# TIMER.net
KiCad netlist of a schematic drawn in Altium Designer
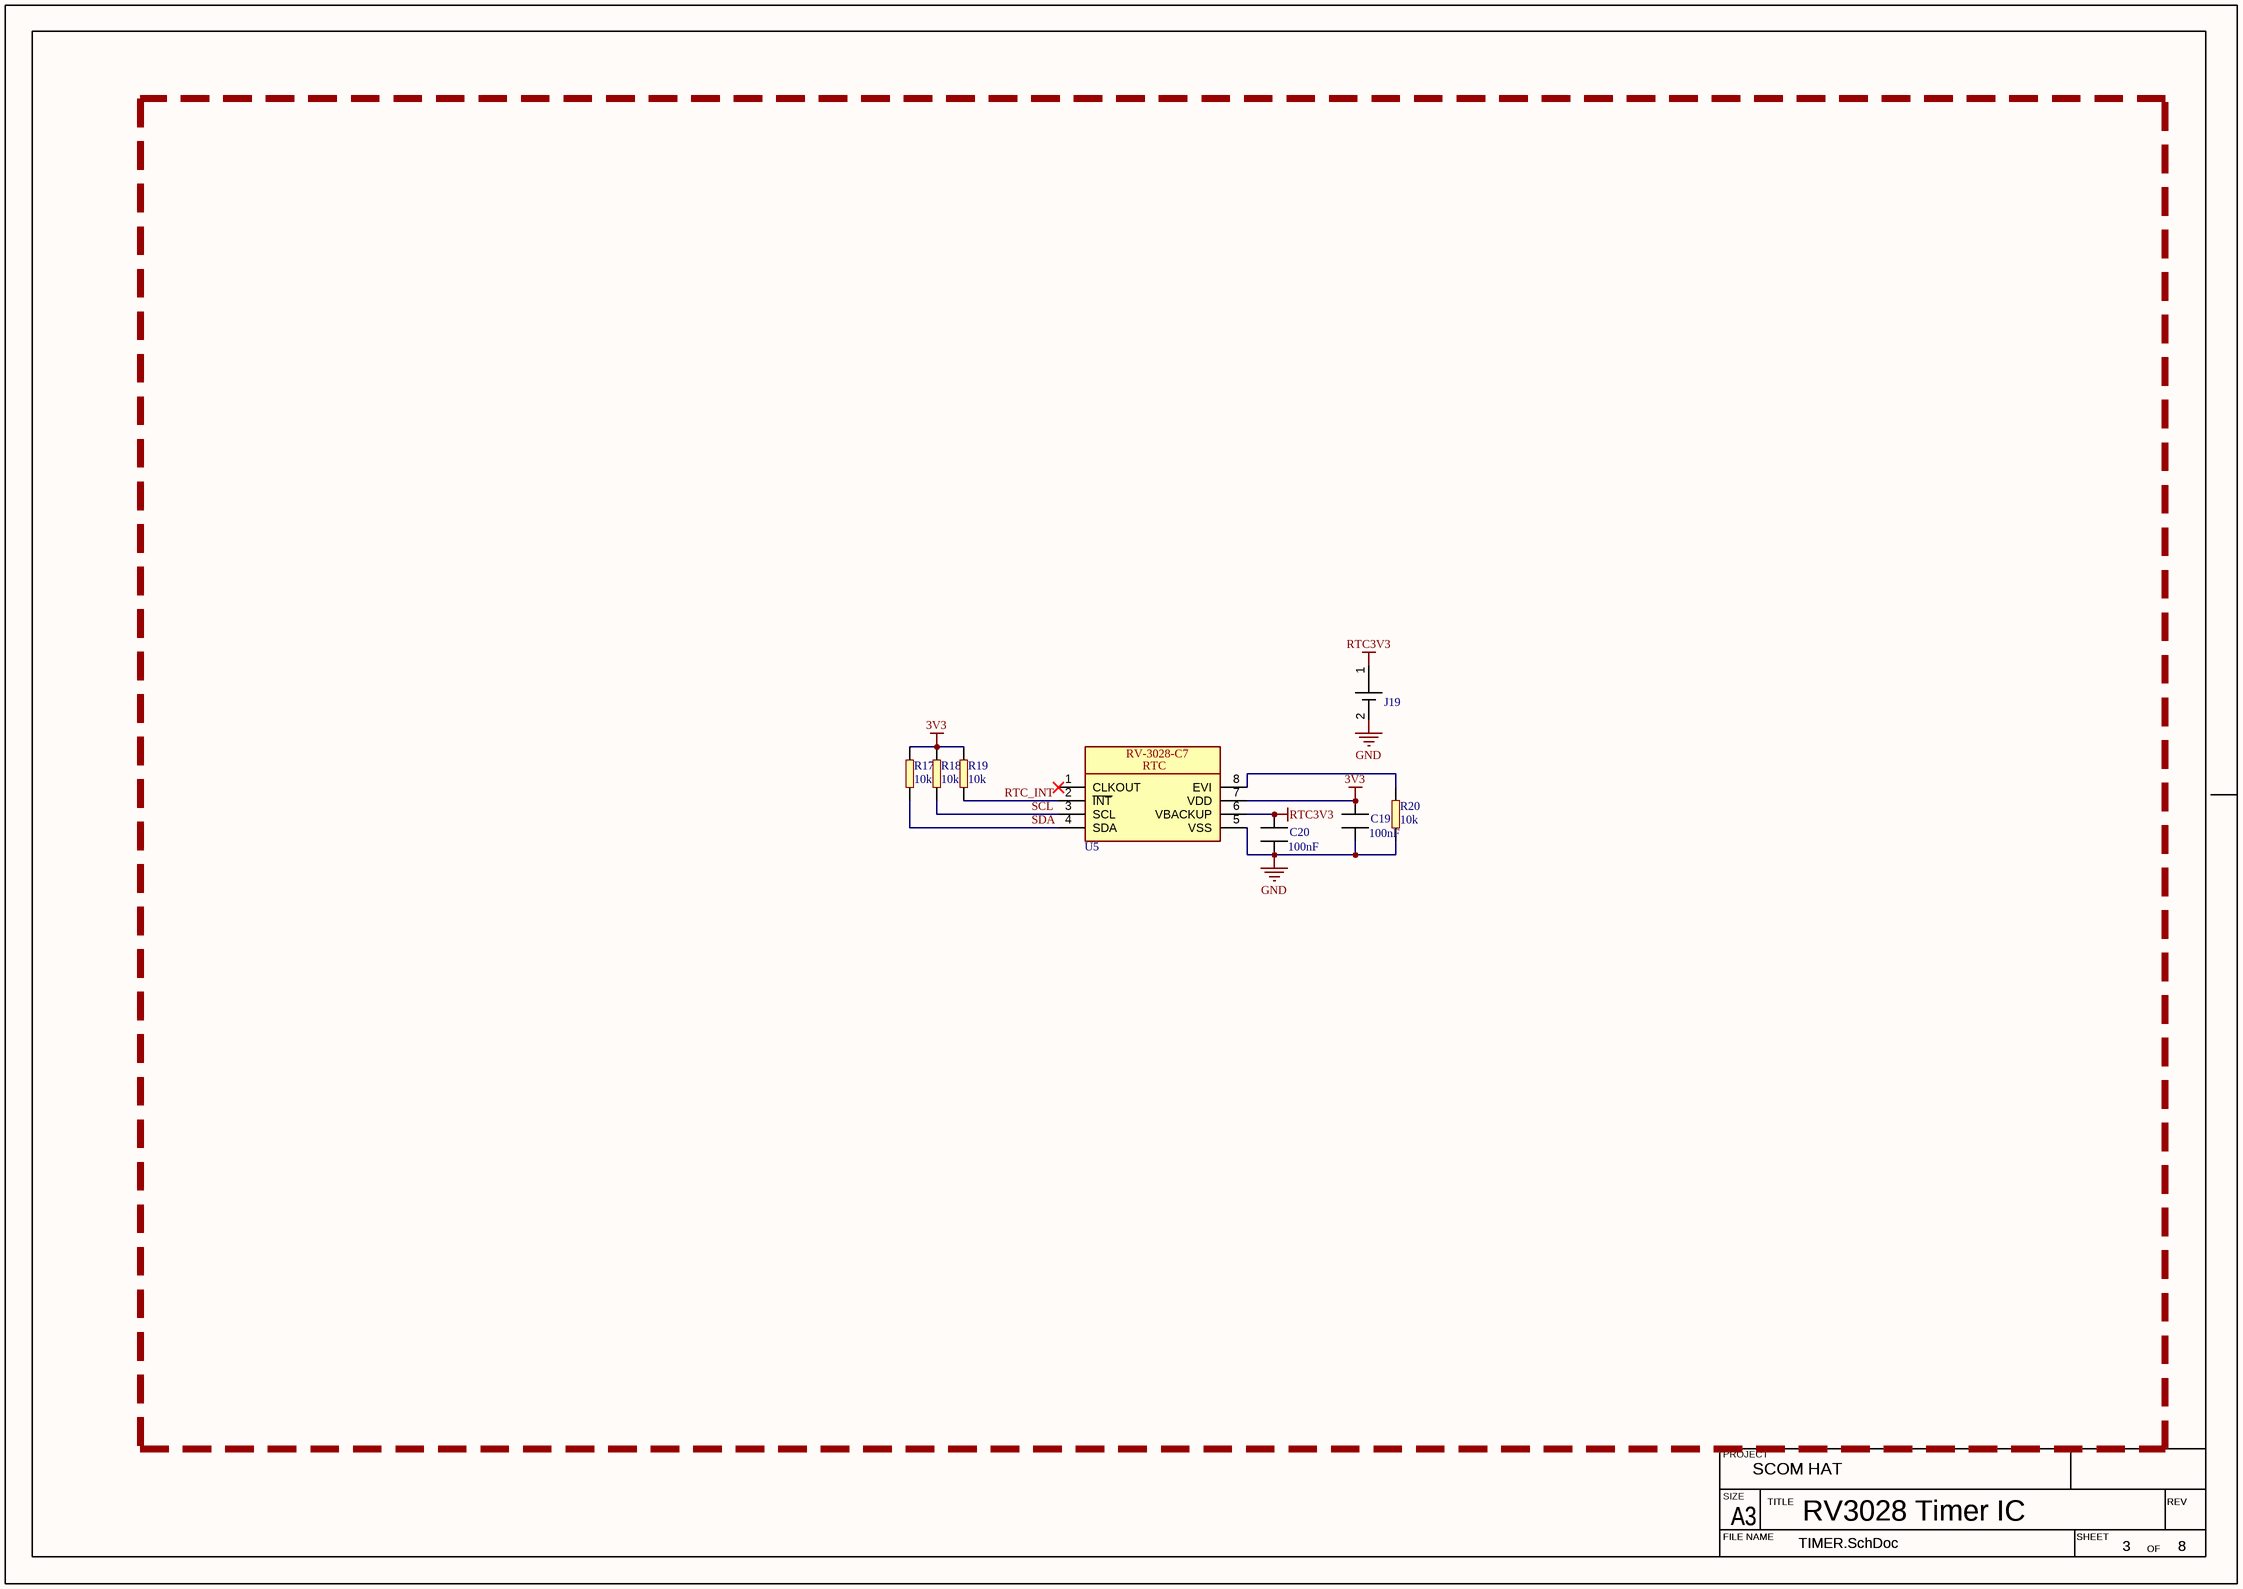
[diagram p0: TIMER.SchDoc]

(export (version "E")
  (design (tool "Eeschema 10.0.6"))
  (components
    (comp (ref "C19")
      (value "100nF")
      (footprint "CAPC2012X13L")
      (description "1uF 105 0805 (2012 metric) 50V X7R MLCC SMD")
      (fields (field (name "Comment") "MLCC_0805"))
      (libsource (lib "Capacitor") (part "MLCC_0805"))
    )
    (comp (ref "C20")
      (value "100nF")
      (footprint "CAPC2012X13L")
      (description "1uF 105 0805 (2012 metric) 50V X7R MLCC SMD")
      (fields (field (name "Comment") "MLCC_0805"))
      (libsource (lib "Capacitor") (part "MLCC_0805"))
    )
    (comp (ref "J19")
      (value "CR1220-BH")
      (footprint "CR1220-BH")
      (description "BATTERY HOLDER COIN 12.5MM SMD")
      (libsource (lib "Connectors") (part "CR1220-BH"))
    )
    (comp (ref "R17")
      (value "10k")
      (footprint "RES_0603")
      (description "RES_0603")
      (fields (field (name "Comment") "ERP_101-1"))
      (libsource (lib "Resistor") (part "RES_0603"))
    )
    (comp (ref "R18")
      (value "10k")
      (footprint "RES_0603")
      (description "RES_0603")
      (fields (field (name "Comment") "ERP_101-1"))
      (libsource (lib "Resistor") (part "RES_0603"))
    )
    (comp (ref "R19")
      (value "10k")
      (footprint "RES_0603")
      (description "RES_0603")
      (fields (field (name "Comment") "ERP_101-1"))
      (libsource (lib "Resistor") (part "RES_0603"))
    )
    (comp (ref "R20")
      (value "10k")
      (footprint "RES_0603")
      (description "RES_0603")
      (fields (field (name "Comment") "ERP_101-1"))
      (libsource (lib "Resistor") (part "RES_0603"))
    )
    (comp (ref "U5")
      (value "RV-3028-C7")
      (footprint "RV-3028-C7")
      (description "IC RTC CLK/CALENDAR I2C 8SON")
      (libsource (lib "RTC") (part "RV-3028-C7"))
    )
  )
  (nets
    (net (code "1") (name "/RTC_INT") (class "Default")
      (node (ref "R19") (pin "1") (pinfunction "1_1") (pintype "passive"))
      (node (ref "U5") (pin "2") (pinfunction "~{INT}_2") (pintype "passive"))
    )
    (net (code "2") (name "/SCL") (class "Default")
      (node (ref "R18") (pin "1") (pinfunction "1_1") (pintype "passive"))
      (node (ref "U5") (pin "3") (pinfunction "SCL_3") (pintype "passive"))
    )
    (net (code "3") (name "/SDA") (class "Default")
      (node (ref "R17") (pin "1") (pinfunction "1_1") (pintype "passive"))
      (node (ref "U5") (pin "4") (pinfunction "SDA_4") (pintype "passive"))
    )
    (net (code "4") (name "3V3") (class "Default")
      (node (ref "C19") (pin "1") (pinfunction "1_1") (pintype "passive"))
      (node (ref "R17") (pin "2") (pinfunction "2_2") (pintype "passive"))
      (node (ref "R18") (pin "2") (pinfunction "2_2") (pintype "passive"))
      (node (ref "R19") (pin "2") (pinfunction "2_2") (pintype "passive"))
      (node (ref "U5") (pin "7") (pinfunction "VDD_7") (pintype "passive"))
    )
    (net (code "5") (name "GND") (class "Default")
      (node (ref "C19") (pin "2") (pinfunction "2_2") (pintype "passive"))
      (node (ref "C20") (pin "2") (pinfunction "2_2") (pintype "passive"))
      (node (ref "J19") (pin "2") (pinfunction "-_2") (pintype "passive"))
      (node (ref "R20") (pin "1") (pinfunction "1_1") (pintype "passive"))
      (node (ref "U5") (pin "5") (pinfunction "VSS_5") (pintype "passive"))
    )
    (net (code "6") (name "Net-(U5-EVI)") (class "Default")
      (node (ref "R20") (pin "2") (pinfunction "2_2") (pintype "passive"))
      (node (ref "U5") (pin "8") (pinfunction "EVI_8") (pintype "passive"))
    )
    (net (code "7") (name "RTC3V3") (class "Default")
      (node (ref "C20") (pin "1") (pinfunction "1_1") (pintype "passive"))
      (node (ref "J19") (pin "1") (pinfunction "+_1") (pintype "passive"))
      (node (ref "U5") (pin "6") (pinfunction "VBACKUP_6") (pintype "passive"))
    )
    (net (code "8") (name "unconnected-(U5-CLKOUT-Pad1)") (class "Default")
      (node (ref "U5") (pin "1") (pinfunction "CLKOUT_1") (pintype "passive+no_connect"))
    )
  )
)
